# STM32-ROMI_Rev_A_2_Connectors.net
KiCad netlist of a schematic drawn in Altium Designer
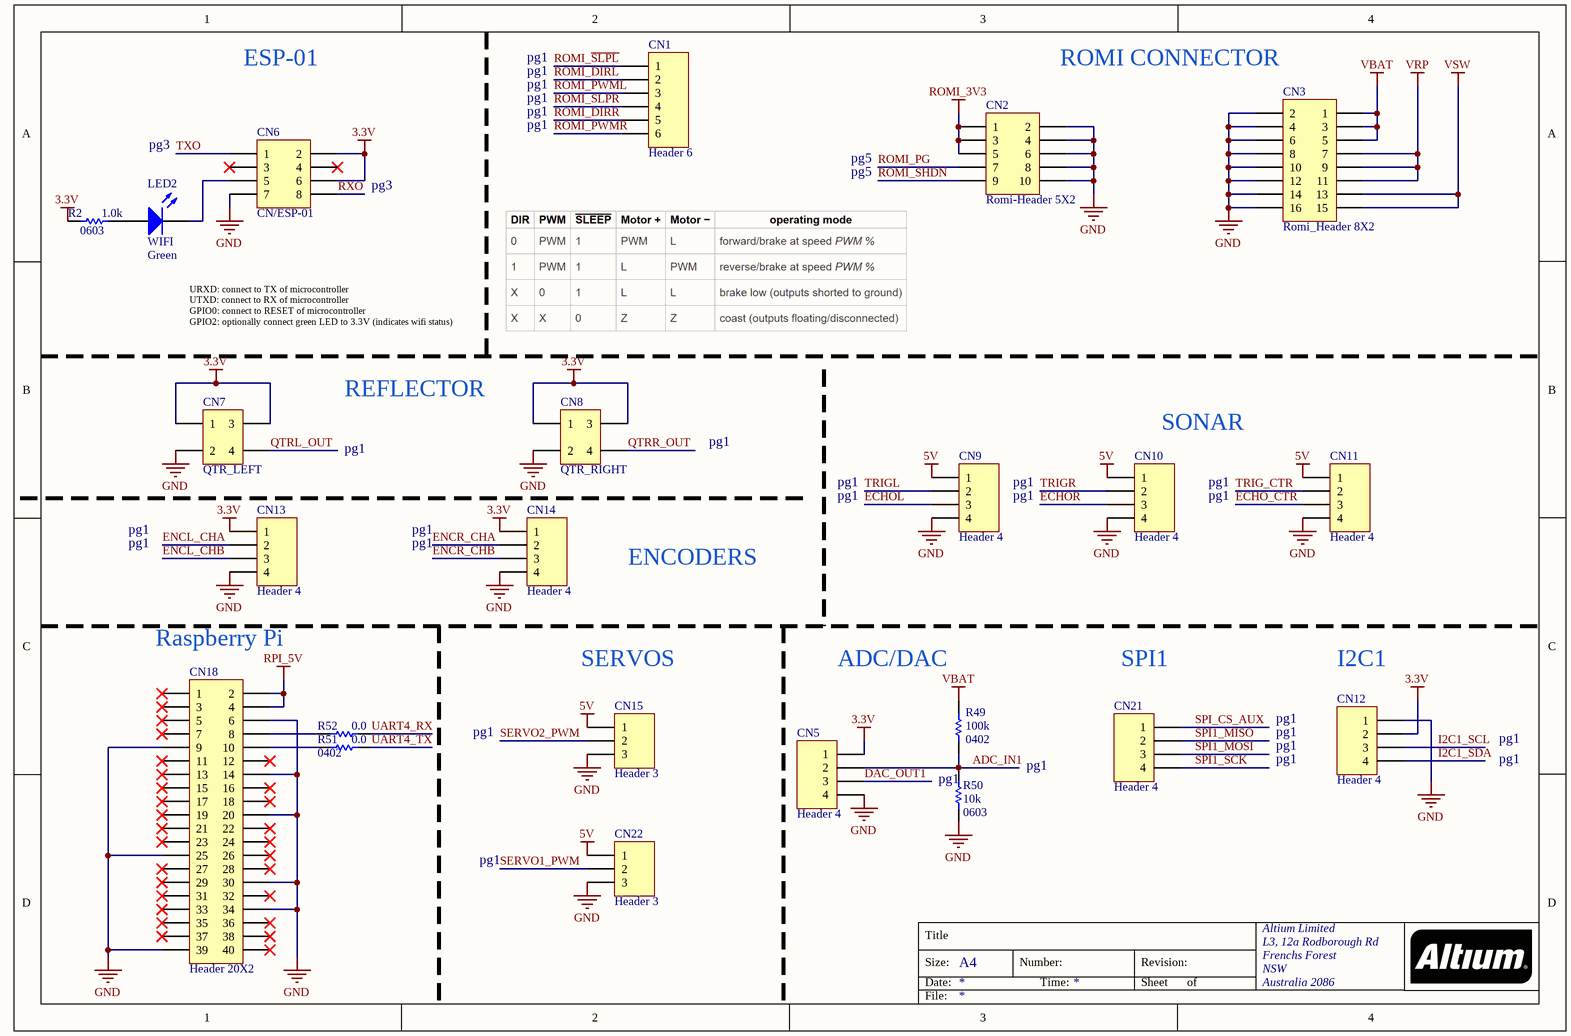
[diagram p0: STM32-ROMI_Rev_A_2_Connectors.SchDoc]

(export (version "E")
  (design (tool "Eeschema 10.0.6"))
  (components
    (comp (ref "CN1")
      (value "Header 6")
      (footprint "PinHeader_1x06_P2.54mm_Vertical")
      (description "Header, 6-Pin")
      (fields
        (field (name "MANUFACTURER") "Sullins Connector Solutions")
        (field (name "MANUFACTURER PART NUMBER") "PRPC006SAAN-RC")
      )
      (libsource (lib "Kyle-Connectors") (part "Romi_Header 6"))
    )
    (comp (ref "CN2")
      (value "Romi-Header 5X2")
      (footprint "PinHeader_2x05_P2.54mm_Vertical - duplicate")
      (description "Header, 5-Pin, Dual row")
      (fields (field (name "PUBLISHER") "Altium Limited"))
      (libsource (lib "Kyle-Connectors") (part "Romi-Header 5X2"))
    )
    (comp (ref "CN3")
      (value "Romi_Header 8X2")
      (footprint "PinHeader_2x08_P2.54mm_Vertical")
      (description "Header, 8-Pin, Dual row")
      (fields (field (name "PUBLISHER") "Altium Limited"))
      (libsource (lib "Kyle-Connectors") (part "Romi_Header 8X2"))
    )
    (comp (ref "CN5")
      (value "Header 4")
      (footprint "HDR1X4")
      (description "Header, 4-Pin")
      (fields
        (field (name "MANUFACTURER") "Sullins Connector Solutions")
        (field (name "MANUFACTURER PART NUMBER") "PRPC004SAAN-RC")
      )
      (libsource (lib "") (part "Header 4_1"))
    )
    (comp (ref "CN6")
      (value "CN/ESP-01")
      (footprint "ESP-01")
      (description "Header, 4-Pin, Dual row")
      (fields (field (name "PUBLISHER") "Altium Limited"))
      (libsource (lib "Kyle_Lib_04-20-19") (part "CN/ESP-01"))
    )
    (comp (ref "CN7")
      (value "QTR_LEFT")
      (footprint "Molex 2x2 Microfit")
      (description "Molex Microfit 2x2 Vert Header")
      (fields
        (field (name "MANUFACTURER") "Molex Inc")
        (field (name "MANUFACTURER PART NUMBER") "0430450427")
      )
      (libsource (lib "OLogic-Connectors") (part "MICROFIT 3.0 HDR VERT 4CKT"))
    )
    (comp (ref "CN8")
      (value "QTR_RIGHT")
      (footprint "Molex 2x2 Microfit")
      (description "Molex Microfit 2x2 Vert Header")
      (fields
        (field (name "MANUFACTURER") "Molex Inc")
        (field (name "MANUFACTURER PART NUMBER") "0430450427")
      )
      (libsource (lib "OLogic-Connectors") (part "MICROFIT 3.0 HDR VERT 4CKT"))
    )
    (comp (ref "CN9")
      (value "Header 4")
      (footprint "HDR1X4")
      (description "Header, 4-Pin")
      (fields
        (field (name "MANUFACTURER") "Sullins Connector Solutions")
        (field (name "MANUFACTURER PART NUMBER") "PRPC004SAAN-RC")
      )
      (libsource (lib "Kyle-Connectors") (part "Header 4"))
    )
    (comp (ref "CN10")
      (value "Header 4")
      (footprint "HDR1X4")
      (description "Header, 4-Pin")
      (fields
        (field (name "MANUFACTURER") "Sullins Connector Solutions")
        (field (name "MANUFACTURER PART NUMBER") "PRPC004SAAN-RC")
      )
      (libsource (lib "Kyle-Connectors") (part "Header 4"))
    )
    (comp (ref "CN11")
      (value "Header 4")
      (footprint "HDR1X4")
      (description "Header, 4-Pin")
      (fields
        (field (name "MANUFACTURER") "Sullins Connector Solutions")
        (field (name "MANUFACTURER PART NUMBER") "PRPC004SAAN-RC")
      )
      (libsource (lib "Kyle-Connectors") (part "Header 4"))
    )
    (comp (ref "CN12")
      (value "Header 4")
      (footprint "HDR1X4")
      (description "Header, 4-Pin")
      (fields
        (field (name "MANUFACTURER") "Sullins Connector Solutions")
        (field (name "MANUFACTURER PART NUMBER") "PRPC004SAAN-RC")
      )
      (libsource (lib "") (part "Header 4_1"))
    )
    (comp (ref "CN13")
      (value "Header 4")
      (footprint "HDR1X4")
      (description "Header, 4-Pin")
      (fields
        (field (name "MANUFACTURER") "Sullins Connector Solutions")
        (field (name "MANUFACTURER PART NUMBER") "PRPC004SAAN-RC")
      )
      (libsource (lib "Kyle-Connectors") (part "Header 4"))
    )
    (comp (ref "CN14")
      (value "Header 4")
      (footprint "HDR1X4")
      (description "Header, 4-Pin")
      (fields
        (field (name "MANUFACTURER") "Sullins Connector Solutions")
        (field (name "MANUFACTURER PART NUMBER") "PRPC004SAAN-RC")
      )
      (libsource (lib "Kyle-Connectors") (part "Header 4"))
    )
    (comp (ref "CN15")
      (value "Header 3")
      (footprint "HDR1X3")
      (description "Header, 3-Pin")
      (fields
        (field (name "MANUFACTURER") "Sullins Connector Solutions")
        (field (name "MANUFACTURER PART NUMBER") "PRPC003SAAN-RC")
      )
      (libsource (lib "Kyle-Connectors") (part "Header 3"))
    )
    (comp (ref "CN18")
      (value "Header 20X2")
      (footprint "Raspberry_Pi_2_3")
      (description "Header, 20-Pin, Dual row")
      (fields
        (field (name "MANUFACTURER") "Harwin Inc")
        (field (name "MANUFACTURER PART NUMBER") "M20-9762046")
      )
      (libsource (lib "Kyle_Lib_04-20-19") (part "J/Header 20X2"))
    )
    (comp (ref "CN21")
      (value "Header 4")
      (footprint "HDR1X4")
      (description "Header, 4-Pin")
      (fields
        (field (name "MANUFACTURER") "Sullins Connector Solutions")
        (field (name "MANUFACTURER PART NUMBER") "PRPC004SAAN-RC")
      )
      (libsource (lib "") (part "Header 4_1"))
    )
    (comp (ref "CN22")
      (value "Header 3")
      (footprint "HDR1X3")
      (description "Header, 3-Pin")
      (fields
        (field (name "MANUFACTURER") "Sullins Connector Solutions")
        (field (name "MANUFACTURER PART NUMBER") "PRPC003SAAN-RC")
      )
      (libsource (lib "Kyle-Connectors") (part "Header 3"))
    )
    (comp (ref "LED2")
      (value "WIFI")
      (footprint "SM-LED-0603")
      (description "LED GREEN CLEAR THIN 0603 SMD")
      (fields
        (field (name "MANUFACTURER") "Lite-On Inc")
        (field (name "MANUFACTURER PART NUMBER") "LTST-C191KGKT")
        (field (name "COLOR") "Green")
      )
      (libsource (lib "Kyle-Diode-Opto-LED") (part "LTST-C191KGKT"))
    )
    (comp (ref "R2")
      (value "1.0K")
      (footprint "RESC0603(1608)_N")
      (description "1.0K 0603")
      (fields
        (field (name "MANUFACTURER") "Stackpole Electronics Inc.")
        (field (name "MANUFACTURER PART NUMBER") "RMCF0603FT1K00")
        (field (name "PACKAGE / CASE") "0603")
        (field (name "RESISTANCE (OHMS)") "1.0k")
      )
      (libsource (lib "Kyle-Passive") (part "RES 1K OHM 1% 1/10W 0603"))
    )
    (comp (ref "R49")
      (value "100K 0402")
      (footprint "RESC0402(1005)_L")
      (fields
        (field (name "MANUFACTURER") "Yageo")
        (field (name "MANUFACTURER PART NUMBER") "RC0402FR-07100KL")
        (field (name "TOLERANCE") "±1%")
        (field (name "SUPPLIER DEVICE PACKAGE") "0402")
        (field (name "RESISTANCE (OHMS)") "100k")
      )
      (libsource (lib "OLogic-Passive") (part "RES 100K OHM 1% 1/16W 0402"))
    )
    (comp (ref "R50")
      (value "10K 1%")
      (footprint "RESC0603(1608)_L")
      (description "10K 0603")
      (fields
        (field (name "MANUFACTURER") "Panasonic Electronic Components")
        (field (name "MANUFACTURER PART NUMBER") "ERJ-3EKF1002V")
        (field (name "RESISTANCE (OHMS)") "10k")
        (field (name "PACKAGE / CASE") "0603")
      )
      (libsource (lib "Kyle-Passive") (part "RES 10K OHM 1/10W 1% 0603 SMD"))
    )
    (comp (ref "R51")
      (value "0")
      (footprint "RESC0402(1005)_L")
      (description "0.0 0402")
      (fields
        (field (name "MANUFACTURER") "Panasonic Electronic Components")
        (field (name "MANUFACTURER PART NUMBER") "ERJ-2GE0R00X")
        (field (name "SUPPLIER DEVICE PACKAGE") "0402")
        (field (name "RESISTANCE (OHMS)") "0.0")
        (field (name "CREATOR") "osman")
      )
      (libsource (lib "OLogic-Passive") (part "RES 0.0 OHM JUMPER 1/10W 0402"))
    )
    (comp (ref "R52")
      (value "0")
      (footprint "RESC0402(1005)_L")
      (description "0.0 0402")
      (fields
        (field (name "MANUFACTURER") "Panasonic Electronic Components")
        (field (name "MANUFACTURER PART NUMBER") "ERJ-2GE0R00X")
        (field (name "RESISTANCE (OHMS)") "0.0")
        (field (name "CREATOR") "osman")
      )
      (libsource (lib "OLogic-Passive") (part "RES 0.0 OHM JUMPER 1/10W 0402"))
    )
  )
  (nets
    (net (code "1") (name "/ADC_IN1") (class "Default")
      (node (ref "CN5") (pin "2") (pinfunction "2_2") (pintype "passive"))
      (node (ref "R49") (pin "1") (pinfunction "1_1") (pintype "passive"))
      (node (ref "R50") (pin "2") (pinfunction "2_2") (pintype "passive"))
    )
    (net (code "2") (name "/DAC_OUT1") (class "Default")
      (node (ref "CN5") (pin "3") (pinfunction "3_3") (pintype "passive"))
    )
    (net (code "3") (name "/ECHOL") (class "Default")
      (node (ref "CN9") (pin "3") (pinfunction "3_3") (pintype "passive"))
    )
    (net (code "4") (name "/ECHOR") (class "Default")
      (node (ref "CN10") (pin "3") (pinfunction "3_3") (pintype "passive"))
    )
    (net (code "5") (name "/ECHO_CTR") (class "Default")
      (node (ref "CN11") (pin "3") (pinfunction "3_3") (pintype "passive"))
    )
    (net (code "6") (name "/ENCL_CHA") (class "Default")
      (node (ref "CN13") (pin "2") (pinfunction "2_2") (pintype "passive"))
    )
    (net (code "7") (name "/ENCL_CHB") (class "Default")
      (node (ref "CN13") (pin "3") (pinfunction "3_3") (pintype "passive"))
    )
    (net (code "8") (name "/ENCR_CHA") (class "Default")
      (node (ref "CN14") (pin "2") (pinfunction "2_2") (pintype "passive"))
    )
    (net (code "9") (name "/ENCR_CHB") (class "Default")
      (node (ref "CN14") (pin "3") (pinfunction "3_3") (pintype "passive"))
    )
    (net (code "10") (name "/I2C1_SCL") (class "Default")
      (node (ref "CN12") (pin "3") (pinfunction "3_3") (pintype "passive"))
    )
    (net (code "11") (name "/I2C1_SDA") (class "Default")
      (node (ref "CN12") (pin "4") (pinfunction "4_4") (pintype "passive"))
    )
    (net (code "12") (name "/QTRL_OUT") (class "Default")
      (node (ref "CN7") (pin "4") (pinfunction "4_4") (pintype "passive"))
    )
    (net (code "13") (name "/QTRR_OUT") (class "Default")
      (node (ref "CN8") (pin "4") (pinfunction "4_4") (pintype "passive"))
    )
    (net (code "14") (name "/ROMI_DIRL") (class "Default")
      (node (ref "CN1") (pin "2") (pinfunction "2_2") (pintype "passive"))
    )
    (net (code "15") (name "/ROMI_DIRR") (class "Default")
      (node (ref "CN1") (pin "5") (pinfunction "5_5") (pintype "passive"))
    )
    (net (code "16") (name "/ROMI_PG") (class "Default")
      (node (ref "CN2") (pin "7") (pinfunction "7_7") (pintype "passive"))
    )
    (net (code "17") (name "/ROMI_PWML") (class "Default")
      (node (ref "CN1") (pin "3") (pinfunction "3_3") (pintype "passive"))
    )
    (net (code "18") (name "/ROMI_PWMR") (class "Default")
      (node (ref "CN1") (pin "6") (pinfunction "6_6") (pintype "passive"))
    )
    (net (code "19") (name "/ROMI_SHDN") (class "Default")
      (node (ref "CN2") (pin "9") (pinfunction "9_9") (pintype "passive"))
    )
    (net (code "20") (name "/ROMI_~{SLPL}") (class "Default")
      (node (ref "CN1") (pin "1") (pinfunction "1_1") (pintype "passive"))
    )
    (net (code "21") (name "/ROMI_~{SLPR}") (class "Default")
      (node (ref "CN1") (pin "4") (pinfunction "4_4") (pintype "passive"))
    )
    (net (code "22") (name "/RXO") (class "Default")
      (node (ref "CN6") (pin "8") (pinfunction "8_8") (pintype "passive"))
    )
    (net (code "23") (name "/SERVO1_PWM") (class "Default")
      (node (ref "CN22") (pin "2") (pinfunction "2_2") (pintype "passive"))
    )
    (net (code "24") (name "/SERVO2_PWM") (class "Default")
      (node (ref "CN15") (pin "2") (pinfunction "2_2") (pintype "passive"))
    )
    (net (code "25") (name "/SPI1_MISO") (class "Default")
      (node (ref "CN21") (pin "2") (pinfunction "2_2") (pintype "passive"))
    )
    (net (code "26") (name "/SPI1_MOSI") (class "Default")
      (node (ref "CN21") (pin "3") (pinfunction "3_3") (pintype "passive"))
    )
    (net (code "27") (name "/SPI1_SCK") (class "Default")
      (node (ref "CN21") (pin "4") (pinfunction "4_4") (pintype "passive"))
    )
    (net (code "28") (name "/SPI_CS_AUX") (class "Default")
      (node (ref "CN21") (pin "1") (pinfunction "1_1") (pintype "passive"))
    )
    (net (code "29") (name "/TRIGL") (class "Default")
      (node (ref "CN9") (pin "2") (pinfunction "2_2") (pintype "passive"))
    )
    (net (code "30") (name "/TRIGR") (class "Default")
      (node (ref "CN10") (pin "2") (pinfunction "2_2") (pintype "passive"))
    )
    (net (code "31") (name "/TRIG_CTR") (class "Default")
      (node (ref "CN11") (pin "2") (pinfunction "2_2") (pintype "passive"))
    )
    (net (code "32") (name "/TXO") (class "Default")
      (node (ref "CN6") (pin "1") (pinfunction "1_1") (pintype "passive"))
    )
    (net (code "33") (name "/UART4_RX") (class "Default")
      (node (ref "R52") (pin "1") (pinfunction "1_1") (pintype "passive"))
    )
    (net (code "34") (name "/UART4_TX") (class "Default")
      (node (ref "R51") (pin "1") (pinfunction "1_1") (pintype "passive"))
    )
    (net (code "35") (name "3.3V") (class "Default")
      (node (ref "CN12") (pin "2") (pinfunction "2_2") (pintype "passive"))
      (node (ref "CN13") (pin "1") (pinfunction "1_1") (pintype "passive"))
      (node (ref "CN14") (pin "1") (pinfunction "1_1") (pintype "passive"))
      (node (ref "CN5") (pin "1") (pinfunction "1_1") (pintype "passive"))
      (node (ref "CN6") (pin "2") (pinfunction "2_2") (pintype "passive"))
      (node (ref "CN6") (pin "6") (pinfunction "6_6") (pintype "passive"))
      (node (ref "CN7") (pin "1") (pinfunction "1_1") (pintype "passive"))
      (node (ref "CN7") (pin "3") (pinfunction "3_3") (pintype "passive"))
      (node (ref "CN8") (pin "1") (pinfunction "1_1") (pintype "passive"))
      (node (ref "CN8") (pin "3") (pinfunction "3_3") (pintype "passive"))
      (node (ref "R2") (pin "2") (pinfunction "2_2") (pintype "passive"))
    )
    (net (code "36") (name "5V") (class "Default")
      (node (ref "CN10") (pin "1") (pinfunction "1_1") (pintype "passive"))
      (node (ref "CN11") (pin "1") (pinfunction "1_1") (pintype "passive"))
      (node (ref "CN15") (pin "1") (pinfunction "1_1") (pintype "passive"))
      (node (ref "CN22") (pin "1") (pinfunction "1_1") (pintype "passive"))
      (node (ref "CN9") (pin "1") (pinfunction "1_1") (pintype "passive"))
    )
    (net (code "37") (name "GND") (class "Default")
      (node (ref "CN10") (pin "4") (pinfunction "4_4") (pintype "passive"))
      (node (ref "CN11") (pin "4") (pinfunction "4_4") (pintype "passive"))
      (node (ref "CN12") (pin "1") (pinfunction "1_1") (pintype "passive"))
      (node (ref "CN13") (pin "4") (pinfunction "4_4") (pintype "passive"))
      (node (ref "CN14") (pin "4") (pinfunction "4_4") (pintype "passive"))
      (node (ref "CN15") (pin "3") (pinfunction "3_3") (pintype "passive"))
      (node (ref "CN18") (pin "14") (pinfunction "14_14") (pintype "passive"))
      (node (ref "CN18") (pin "20") (pinfunction "20_20") (pintype "passive"))
      (node (ref "CN18") (pin "25") (pinfunction "25_25") (pintype "passive"))
      (node (ref "CN18") (pin "30") (pinfunction "30_30") (pintype "passive"))
      (node (ref "CN18") (pin "34") (pinfunction "34_34") (pintype "passive"))
      (node (ref "CN18") (pin "39") (pinfunction "39_39") (pintype "passive"))
      (node (ref "CN18") (pin "6") (pinfunction "6_6") (pintype "passive"))
      (node (ref "CN18") (pin "9") (pinfunction "9_9") (pintype "passive"))
      (node (ref "CN2") (pin "10") (pinfunction "10_10") (pintype "passive"))
      (node (ref "CN2") (pin "2") (pinfunction "2_2") (pintype "passive"))
      (node (ref "CN2") (pin "4") (pinfunction "4_4") (pintype "passive"))
      (node (ref "CN2") (pin "6") (pinfunction "6_6") (pintype "passive"))
      (node (ref "CN2") (pin "8") (pinfunction "8_8") (pintype "passive"))
      (node (ref "CN22") (pin "3") (pinfunction "3_3") (pintype "passive"))
      (node (ref "CN3") (pin "10") (pinfunction "10_10") (pintype "passive"))
      (node (ref "CN3") (pin "12") (pinfunction "12_12") (pintype "passive"))
      (node (ref "CN3") (pin "14") (pinfunction "14_14") (pintype "passive"))
      (node (ref "CN3") (pin "16") (pinfunction "16_16") (pintype "passive"))
      (node (ref "CN3") (pin "2") (pinfunction "2_2") (pintype "passive"))
      (node (ref "CN3") (pin "4") (pinfunction "4_4") (pintype "passive"))
      (node (ref "CN3") (pin "6") (pinfunction "6_6") (pintype "passive"))
      (node (ref "CN3") (pin "8") (pinfunction "8_8") (pintype "passive"))
      (node (ref "CN5") (pin "4") (pinfunction "4_4") (pintype "passive"))
      (node (ref "CN6") (pin "7") (pinfunction "7_7") (pintype "passive"))
      (node (ref "CN7") (pin "2") (pinfunction "2_2") (pintype "passive"))
      (node (ref "CN8") (pin "2") (pinfunction "2_2") (pintype "passive"))
      (node (ref "CN9") (pin "4") (pinfunction "4_4") (pintype "passive"))
      (node (ref "R50") (pin "1") (pinfunction "1_1") (pintype "passive"))
    )
    (net (code "38") (name "Net-(CN6-Pad5)") (class "Default")
      (node (ref "CN6") (pin "5") (pinfunction "5_5") (pintype "passive"))
      (node (ref "LED2") (pin "2") (pinfunction "2_2") (pintype "passive"))
    )
    (net (code "39") (name "Net-(CN18-Pad8)") (class "Default")
      (node (ref "CN18") (pin "8") (pinfunction "8_8") (pintype "passive"))
      (node (ref "R52") (pin "2") (pinfunction "2_2") (pintype "passive"))
    )
    (net (code "40") (name "Net-(CN18-Pad10)") (class "Default")
      (node (ref "CN18") (pin "10") (pinfunction "10_10") (pintype "passive"))
      (node (ref "R51") (pin "2") (pinfunction "2_2") (pintype "passive"))
    )
    (net (code "41") (name "Net-(LED2-Pad1)") (class "Default")
      (node (ref "LED2") (pin "1") (pinfunction "1_1") (pintype "passive"))
      (node (ref "R2") (pin "1") (pinfunction "1_1") (pintype "passive"))
    )
    (net (code "42") (name "ROMI_3V3") (class "Default")
      (node (ref "CN2") (pin "1") (pinfunction "1_1") (pintype "passive"))
      (node (ref "CN2") (pin "3") (pinfunction "3_3") (pintype "passive"))
      (node (ref "CN2") (pin "5") (pinfunction "5_5") (pintype "passive"))
    )
    (net (code "43") (name "RPI_5V") (class "Default")
      (node (ref "CN18") (pin "2") (pinfunction "2_2") (pintype "passive"))
      (node (ref "CN18") (pin "4") (pinfunction "4_4") (pintype "passive"))
    )
    (net (code "44") (name "VBAT") (class "Default")
      (node (ref "CN3") (pin "1") (pinfunction "1_1") (pintype "passive"))
      (node (ref "CN3") (pin "3") (pinfunction "3_3") (pintype "passive"))
      (node (ref "CN3") (pin "5") (pinfunction "5_5") (pintype "passive"))
      (node (ref "R49") (pin "2") (pinfunction "2_2") (pintype "passive"))
    )
    (net (code "45") (name "VRP") (class "Default")
      (node (ref "CN3") (pin "11") (pinfunction "11_11") (pintype "passive"))
      (node (ref "CN3") (pin "7") (pinfunction "7_7") (pintype "passive"))
      (node (ref "CN3") (pin "9") (pinfunction "9_9") (pintype "passive"))
    )
    (net (code "46") (name "VSW") (class "Default")
      (node (ref "CN3") (pin "13") (pinfunction "13_13") (pintype "passive"))
      (node (ref "CN3") (pin "15") (pinfunction "15_15") (pintype "passive"))
    )
    (net (code "47") (name "unconnected-(CN6-Pad3)") (class "Default")
      (node (ref "CN6") (pin "3") (pinfunction "3_3") (pintype "passive+no_connect"))
    )
    (net (code "48") (name "unconnected-(CN6-Pad4)") (class "Default")
      (node (ref "CN6") (pin "4") (pinfunction "4_4") (pintype "passive+no_connect"))
    )
    (net (code "49") (name "unconnected-(CN18-Pad1)") (class "Default")
      (node (ref "CN18") (pin "1") (pinfunction "1_1") (pintype "passive+no_connect"))
    )
    (net (code "50") (name "unconnected-(CN18-Pad3)") (class "Default")
      (node (ref "CN18") (pin "3") (pinfunction "3_3") (pintype "passive+no_connect"))
    )
    (net (code "51") (name "unconnected-(CN18-Pad5)") (class "Default")
      (node (ref "CN18") (pin "5") (pinfunction "5_5") (pintype "passive+no_connect"))
    )
    (net (code "52") (name "unconnected-(CN18-Pad7)") (class "Default")
      (node (ref "CN18") (pin "7") (pinfunction "7_7") (pintype "passive+no_connect"))
    )
    (net (code "53") (name "unconnected-(CN18-Pad11)") (class "Default")
      (node (ref "CN18") (pin "11") (pinfunction "11_11") (pintype "passive+no_connect"))
    )
    (net (code "54") (name "unconnected-(CN18-Pad12)") (class "Default")
      (node (ref "CN18") (pin "12") (pinfunction "12_12") (pintype "passive+no_connect"))
    )
    (net (code "55") (name "unconnected-(CN18-Pad13)") (class "Default")
      (node (ref "CN18") (pin "13") (pinfunction "13_13") (pintype "passive+no_connect"))
    )
    (net (code "56") (name "unconnected-(CN18-Pad15)") (class "Default")
      (node (ref "CN18") (pin "15") (pinfunction "15_15") (pintype "passive+no_connect"))
    )
    (net (code "57") (name "unconnected-(CN18-Pad16)") (class "Default")
      (node (ref "CN18") (pin "16") (pinfunction "16_16") (pintype "passive+no_connect"))
    )
    (net (code "58") (name "unconnected-(CN18-Pad17)") (class "Default")
      (node (ref "CN18") (pin "17") (pinfunction "17_17") (pintype "passive+no_connect"))
    )
    (net (code "59") (name "unconnected-(CN18-Pad18)") (class "Default")
      (node (ref "CN18") (pin "18") (pinfunction "18_18") (pintype "passive+no_connect"))
    )
    (net (code "60") (name "unconnected-(CN18-Pad19)") (class "Default")
      (node (ref "CN18") (pin "19") (pinfunction "19_19") (pintype "passive+no_connect"))
    )
    (net (code "61") (name "unconnected-(CN18-Pad21)") (class "Default")
      (node (ref "CN18") (pin "21") (pinfunction "21_21") (pintype "passive+no_connect"))
    )
    (net (code "62") (name "unconnected-(CN18-Pad22)") (class "Default")
      (node (ref "CN18") (pin "22") (pinfunction "22_22") (pintype "passive+no_connect"))
    )
    (net (code "63") (name "unconnected-(CN18-Pad23)") (class "Default")
      (node (ref "CN18") (pin "23") (pinfunction "23_23") (pintype "passive+no_connect"))
    )
    (net (code "64") (name "unconnected-(CN18-Pad24)") (class "Default")
      (node (ref "CN18") (pin "24") (pinfunction "24_24") (pintype "passive+no_connect"))
    )
    (net (code "65") (name "unconnected-(CN18-Pad26)") (class "Default")
      (node (ref "CN18") (pin "26") (pinfunction "26_26") (pintype "passive+no_connect"))
    )
    (net (code "66") (name "unconnected-(CN18-Pad27)") (class "Default")
      (node (ref "CN18") (pin "27") (pinfunction "27_27") (pintype "passive+no_connect"))
    )
    (net (code "67") (name "unconnected-(CN18-Pad28)") (class "Default")
      (node (ref "CN18") (pin "28") (pinfunction "28_28") (pintype "passive+no_connect"))
    )
    (net (code "68") (name "unconnected-(CN18-Pad29)") (class "Default")
      (node (ref "CN18") (pin "29") (pinfunction "29_29") (pintype "passive+no_connect"))
    )
    (net (code "69") (name "unconnected-(CN18-Pad31)") (class "Default")
      (node (ref "CN18") (pin "31") (pinfunction "31_31") (pintype "passive+no_connect"))
    )
    (net (code "70") (name "unconnected-(CN18-Pad32)") (class "Default")
      (node (ref "CN18") (pin "32") (pinfunction "32_32") (pintype "passive+no_connect"))
    )
    (net (code "71") (name "unconnected-(CN18-Pad33)") (class "Default")
      (node (ref "CN18") (pin "33") (pinfunction "33_33") (pintype "passive+no_connect"))
    )
    (net (code "72") (name "unconnected-(CN18-Pad35)") (class "Default")
      (node (ref "CN18") (pin "35") (pinfunction "35_35") (pintype "passive+no_connect"))
    )
    (net (code "73") (name "unconnected-(CN18-Pad36)") (class "Default")
      (node (ref "CN18") (pin "36") (pinfunction "36_36") (pintype "passive+no_connect"))
    )
    (net (code "74") (name "unconnected-(CN18-Pad37)") (class "Default")
      (node (ref "CN18") (pin "37") (pinfunction "37_37") (pintype "passive+no_connect"))
    )
    (net (code "75") (name "unconnected-(CN18-Pad38)") (class "Default")
      (node (ref "CN18") (pin "38") (pinfunction "38_38") (pintype "passive+no_connect"))
    )
    (net (code "76") (name "unconnected-(CN18-Pad40)") (class "Default")
      (node (ref "CN18") (pin "40") (pinfunction "40_40") (pintype "passive+no_connect"))
    )
  )
)
